# Power_Supply.net
KiCad netlist of a schematic drawn in Altium Designer
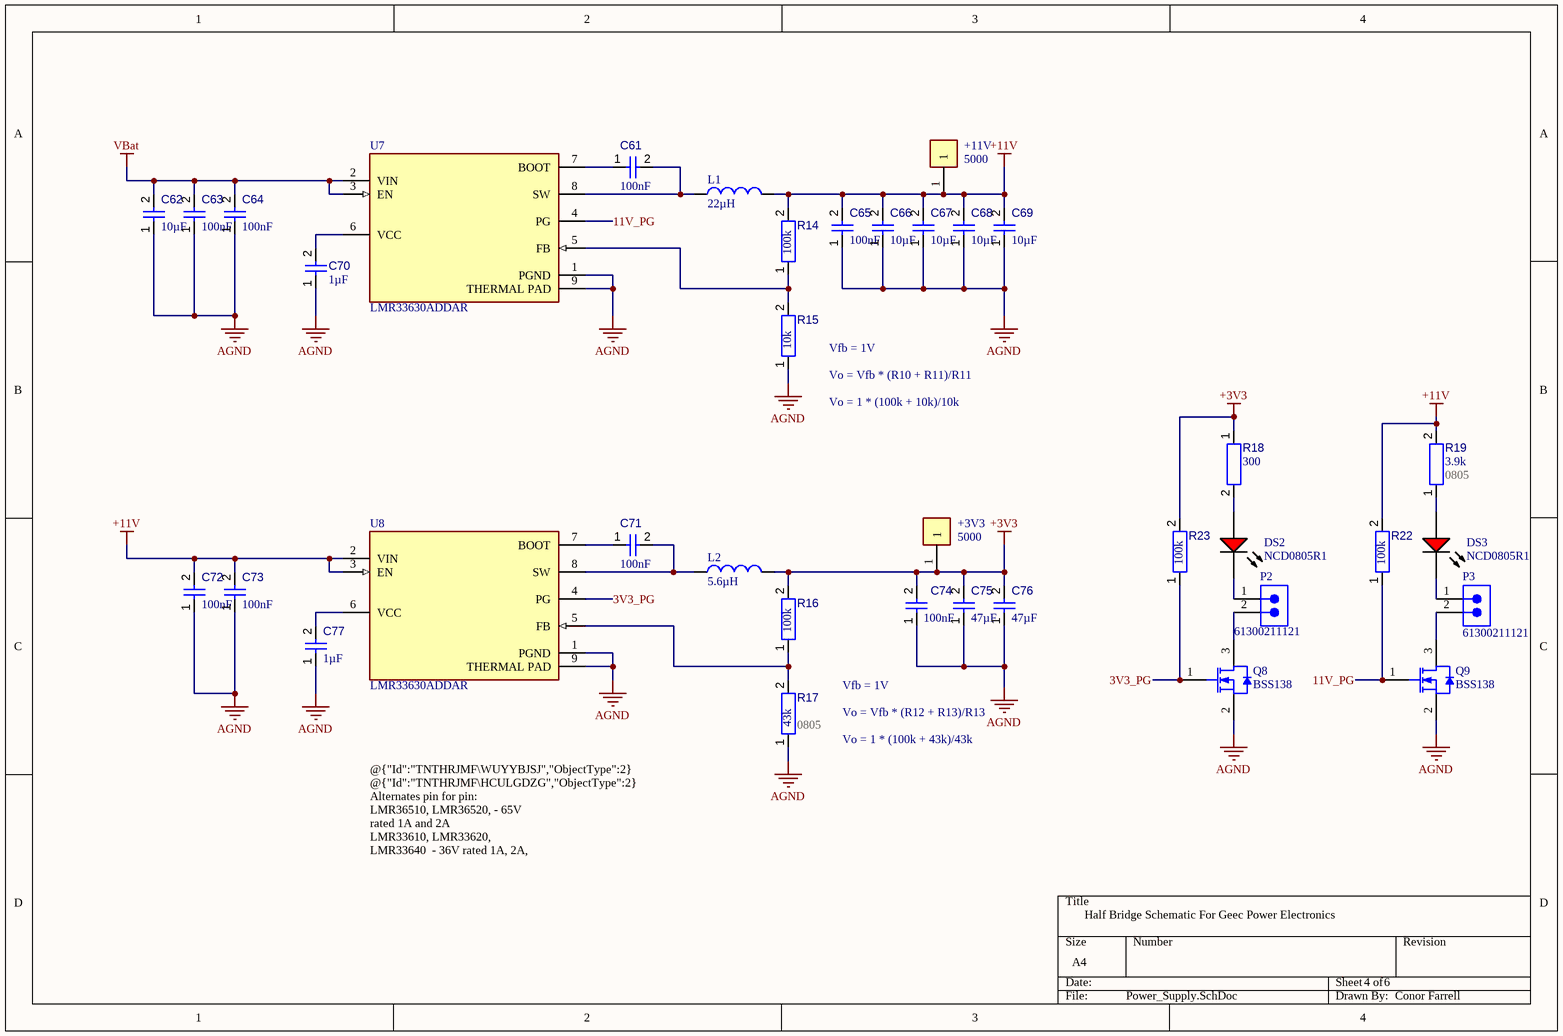
[diagram p0: Power_Supply.SchDoc]

(export (version "E")
  (design (tool "Eeschema 10.0.6"))
  (components
    (comp (ref "+3V3")
      (value "5000")
      (footprint "FP-5000-MFG")
      (description "Cable Wrap, 1/2 Inch, Polyethylene, Natural, 50 Ft, Spirap Series")
      (libsource (lib "University of Galway") (part "1e4615820a309e3ce90f9e6d957b7fa"))
    )
    (comp (ref "+11V")
      (value "5000")
      (footprint "FP-5000-MFG")
      (description "Cable Wrap, 1/2 Inch, Polyethylene, Natural, 50 Ft, Spirap Series")
      (libsource (lib "University of Galway") (part "1e4615820a309e3ce90f9e6d957b7fa"))
    )
    (comp (ref "C61")
      (value "100nF")
      (footprint "CAPC3216X190X55ML30T25")
      (description "50V 100nF X7R ±10% 1206 Multilayer Ceramic Capacitors MLCC - SMD/SMT ROHS")
      (fields (field (name "TOLERANCE") "10%") (field (name "Comment") "CL31B104KBCNNNC"))
      (libsource (lib "University of Galway") (part "CAP-NP-2"))
    )
    (comp (ref "C62")
      (value "10µF")
      (footprint "FP-GCM32E-0_3-IPC_C")
      (description "50V 10uF X7S ±10% 1210 Multilayer Ceramic Capacitors MLCC - SMD/SMT ROHS")
      (fields (field (name "TOLERANCE") "10%") (field (name "Comment") "GCM32EC71H106KA03L"))
      (libsource (lib "University of Galway") (part "CAP-NP-2"))
    )
    (comp (ref "C63")
      (value "100nF")
      (footprint "CAPC3216X190X55ML30T25")
      (description "50V 100nF X7R ±10% 1206 Multilayer Ceramic Capacitors MLCC - SMD/SMT ROHS")
      (fields (field (name "TOLERANCE") "10%") (field (name "Comment") "CL31B104KBCNNNC"))
      (libsource (lib "University of Galway") (part "CAP-NP-2"))
    )
    (comp (ref "C64")
      (value "100nF")
      (footprint "CAPC3216X190X55ML30T25")
      (description "50V 100nF X7R ±10% 1206 Multilayer Ceramic Capacitors MLCC - SMD/SMT ROHS")
      (fields (field (name "TOLERANCE") "10%") (field (name "Comment") "CL31B104KBCNNNC"))
      (libsource (lib "University of Galway") (part "CAP-NP-2"))
    )
    (comp (ref "C65")
      (value "100nF")
      (footprint "CAPC3216X190X55ML30T25")
      (description "50V 100nF X7R ±10% 1206 Multilayer Ceramic Capacitors MLCC - SMD/SMT ROHS")
      (fields (field (name "TOLERANCE") "10%") (field (name "Comment") "CL31B104KBCNNNC"))
      (libsource (lib "University of Galway") (part "CAP-NP-2"))
    )
    (comp (ref "C66")
      (value "10µF")
      (footprint "FP-GCM32E-0_3-IPC_C")
      (description "50V 10uF X7S ±10% 1210 Multilayer Ceramic Capacitors MLCC - SMD/SMT ROHS")
      (fields (field (name "TOLERANCE") "10%") (field (name "Comment") "GCM32EC71H106KA03L"))
      (libsource (lib "University of Galway") (part "CAP-NP-2"))
    )
    (comp (ref "C67")
      (value "10µF")
      (footprint "FP-GCM32E-0_3-IPC_C")
      (description "50V 10uF X7S ±10% 1210 Multilayer Ceramic Capacitors MLCC - SMD/SMT ROHS")
      (fields (field (name "TOLERANCE") "10%") (field (name "Comment") "GCM32EC71H106KA03L"))
      (libsource (lib "University of Galway") (part "CAP-NP-2"))
    )
    (comp (ref "C68")
      (value "10µF")
      (footprint "FP-GCM32E-0_3-IPC_C")
      (description "50V 10uF X7S ±10% 1210 Multilayer Ceramic Capacitors MLCC - SMD/SMT ROHS")
      (fields (field (name "TOLERANCE") "10%") (field (name "Comment") "GCM32EC71H106KA03L"))
      (libsource (lib "University of Galway") (part "CAP-NP-2"))
    )
    (comp (ref "C69")
      (value "10µF")
      (footprint "FP-GCM32E-0_3-IPC_C")
      (description "50V 10uF X7S ±10% 1210 Multilayer Ceramic Capacitors MLCC - SMD/SMT ROHS")
      (fields (field (name "TOLERANCE") "10%") (field (name "Comment") "GCM32EC71H106KA03L"))
      (libsource (lib "University of Galway") (part "CAP-NP-2"))
    )
    (comp (ref "C70")
      (value "1µF")
      (footprint "CAPC3216X180X20ML20")
      (fields (field (name "TOLERANCE") "10%") (field (name "Comment") "CL31B105KBHNNNE"))
      (libsource (lib "University of Galway") (part "CAP-NP-2"))
    )
    (comp (ref "C71")
      (value "100nF")
      (footprint "CAPC3216X190X55ML30T25")
      (description "50V 100nF X7R ±10% 1206 Multilayer Ceramic Capacitors MLCC - SMD/SMT ROHS")
      (fields (field (name "TOLERANCE") "10%") (field (name "Comment") "CL31B104KBCNNNC"))
      (libsource (lib "University of Galway") (part "CAP-NP-2"))
    )
    (comp (ref "C72")
      (value "100nF")
      (footprint "CAPC3216X190X55ML30T25")
      (description "50V 100nF X7R ±10% 1206 Multilayer Ceramic Capacitors MLCC - SMD/SMT ROHS")
      (fields (field (name "TOLERANCE") "10%") (field (name "Comment") "CL31B104KBCNNNC"))
      (libsource (lib "University of Galway") (part "CAP-NP-2"))
    )
    (comp (ref "C73")
      (value "100nF")
      (footprint "CAPC3216X190X55ML30T25")
      (description "50V 100nF X7R ±10% 1206 Multilayer Ceramic Capacitors MLCC - SMD/SMT ROHS")
      (fields (field (name "TOLERANCE") "10%") (field (name "Comment") "CL31B104KBCNNNC"))
      (libsource (lib "University of Galway") (part "CAP-NP-2"))
    )
    (comp (ref "C74")
      (value "100nF")
      (footprint "CAPC3216X190X55ML30T25")
      (description "50V 100nF X7R ±10% 1206 Multilayer Ceramic Capacitors MLCC - SMD/SMT ROHS")
      (fields (field (name "TOLERANCE") "10%") (field (name "Comment") "CL31B104KBCNNNC"))
      (libsource (lib "University of Galway") (part "CAP-NP-2"))
    )
    (comp (ref "C75")
      (value "47µF")
      (footprint "CAPC3216X190X55LL30T25")
      (fields (field (name "TOLERANCE") "20%") (field (name "Comment") "CL31A476MPHNNNE"))
      (libsource (lib "University of Galway") (part "CAP-NP-2"))
    )
    (comp (ref "C76")
      (value "47µF")
      (footprint "CAPC3216X190X55LL30T25")
      (fields (field (name "TOLERANCE") "20%") (field (name "Comment") "CL31A476MPHNNNE"))
      (libsource (lib "University of Galway") (part "CAP-NP-2"))
    )
    (comp (ref "C77")
      (value "1µF")
      (footprint "CAPC3216X180X20ML20")
      (fields (field (name "TOLERANCE") "10%") (field (name "Comment") "CL31B105KBHNNNE"))
      (libsource (lib "University of Galway") (part "CAP-NP-2"))
    )
    (comp (ref "DS2")
      (value "NCD0805R1")
      (footprint "Copy of WL-SMCW_0805_150080xx75000")
      (libsource (lib "University of Galway") (part "LED-RED-AK-2"))
    )
    (comp (ref "DS3")
      (value "NCD0805R1")
      (footprint "Copy of WL-SMCW_0805_150080xx75000")
      (libsource (lib "University of Galway") (part "LED-RED-AK-2"))
    )
    (comp (ref "L1")
      (value "22µH")
      (footprint "INDP127127X85N")
      (description "Inductor Power Shielded Wirewound 22uH 20% 1KHz 23Q-Factor Ferrite 3.5A 0.043Ohm DCR T/R")
      (fields (field (name "TOLERANCE") "20%") (field (name "Comment") "SRR1208-220ML"))
      (libsource (lib "University of Galway") (part "IND-2"))
    )
    (comp (ref "L2")
      (value "5.6µH")
      (footprint "INDP125125X60N")
      (description "Ind Power Shielded Wirewound 5.6uH 30% 100KHz 19Q-Factor Ferrite 6.7A T/R")
      (fields (field (name "TOLERANCE") "30%") (field (name "Comment") "SRR1260A-5R6Y"))
      (libsource (lib "University of Galway") (part "IND-2"))
    )
    (comp (ref "P2")
      (value "61300211121")
      (footprint "61300211121")
      (description "WR-PHD Pin Header, THT, Vertical, pitch 2.54mm, 1 Row, 2P")
      (fields (field (name "MANUFACTURER") "Wurth Elektronik"))
      (libsource (lib "University of Galway") (part "62000211121"))
    )
    (comp (ref "P3")
      (value "61300211121")
      (footprint "61300211121")
      (description "WR-PHD Pin Header, THT, Vertical, pitch 2.54mm, 1 Row, 2P")
      (fields (field (name "MANUFACTURER") "Wurth Elektronik"))
      (libsource (lib "University of Galway") (part "62000211121"))
    )
    (comp (ref "Q8")
      (value "BSS138")
      (footprint "FAIR-SOT23-3_V")
      (fields (field (name "MANUFACTURER") "Fairchild") (field (name "POWER") "360mW"))
      (libsource (lib "University of Galway") (part "NEMOS-GSD-3"))
    )
    (comp (ref "Q9")
      (value "BSS138")
      (footprint "FAIR-SOT23-3_V")
      (fields (field (name "MANUFACTURER") "Fairchild") (field (name "POWER") "360mW"))
      (libsource (lib "University of Galway") (part "NEMOS-GSD-3"))
    )
    (comp (ref "R14")
      (value "100k")
      (footprint "RESC3216X60X45NL15T20")
      (fields (field (name "TOLERANCE") "1%") (field (name "Comment") "1206W4F1003T5E"))
      (libsource (lib "University of Galway") (part "RES-2"))
    )
    (comp (ref "R15")
      (value "10k")
      (footprint "RESC3216X60X45ML15T20")
      (description "Res Thick Film 1206 10K Ohm 1% 0.25W(1/4W) ±100ppm/C Pad SMD T/R")
      (fields (field (name "Comment") "1206W4F1002T5E"))
      (libsource (lib "University of Galway") (part "RES-2"))
    )
    (comp (ref "R16")
      (value "100k")
      (footprint "RESC3216X60X45NL15T20")
      (fields (field (name "TOLERANCE") "1%") (field (name "Comment") "1206W4F1003T5E"))
      (libsource (lib "University of Galway") (part "RES-2"))
    )
    (comp (ref "R17")
      (value "43k")
      (footprint "RESC0805(2012)_L")
      (description "125mW Thick Film Resistors 150V ±100ppm/℃ ±1% 43kΩ 0805 Chip Resistor - Surface Mount ROHS")
      (fields
        (field (name "TOLERANCE") "1%")
        (field (name "POWER") "125mW")
        (field (name "CASE/PACKAGE") "0805")
      )
      (libsource (lib "University of Galway") (part "RES-2"))
    )
    (comp (ref "R18")
      (value "300")
      (footprint "RESC3216X89X51NL25T25")
      (description "250mW Thick Film Resistors 200V ±100ppm/℃ ±1% 300Ω 1206 Chip Resistor - Surface Mount ROHS")
      (fields (field (name "Comment") "1206W4F3000T5E"))
      (libsource (lib "University of Galway") (part "RES-2"))
    )
    (comp (ref "R19")
      (value "3.9k")
      (footprint "RESC2013X60X35ML10T20")
      (description "Res Thick Film 0805 3.9K Ohm 1% 0.125W(1/8W) ±100ppm/C Pad SMD T/R")
      (fields
        (field (name "CASE/PACKAGE") "0805")
        (field (name "POWER") "125mW")
        (field (name "Comment") "0805W8F3901T5E")
      )
      (libsource (lib "University of Galway") (part "RES-2"))
    )
    (comp (ref "R22")
      (value "100k")
      (footprint "RESC3216X60X45NL15T20")
      (fields (field (name "TOLERANCE") "1%") (field (name "Comment") "1206W4F1003T5E"))
      (libsource (lib "University of Galway") (part "RES-2"))
    )
    (comp (ref "R23")
      (value "100k")
      (footprint "RESC3216X60X45NL15T20")
      (fields (field (name "TOLERANCE") "1%") (field (name "Comment") "1206W4F1003T5E"))
      (libsource (lib "University of Galway") (part "RES-2"))
    )
    (comp (ref "U7")
      (value "LMR33630ADDAR")
      (footprint "SOIC127P600X170_HS-9N")
      (libsource (lib "University of Galway") (part "6a354f5098e7f60ae670b755afcc2ec"))
    )
    (comp (ref "U8")
      (value "LMR33630ADDAR")
      (footprint "SOIC127P600X170_HS-9N")
      (libsource (lib "University of Galway") (part "6a354f5098e7f60ae670b755afcc2ec"))
    )
  )
  (nets
    (net (code "1") (name "+3V3") (class "Default")
      (node (ref "+3V3") (pin "1") (pinfunction "1_1") (pintype "passive"))
      (node (ref "C74") (pin "2") (pinfunction "2_2") (pintype "passive"))
      (node (ref "C75") (pin "2") (pinfunction "2_2") (pintype "passive"))
      (node (ref "C76") (pin "2") (pinfunction "2_2") (pintype "passive"))
      (node (ref "L2") (pin "2") (pinfunction "2_2") (pintype "passive"))
      (node (ref "R16") (pin "2") (pinfunction "2_2") (pintype "passive"))
      (node (ref "R18") (pin "1") (pinfunction "1_1") (pintype "passive"))
      (node (ref "R23") (pin "2") (pinfunction "2_2") (pintype "passive"))
    )
    (net (code "2") (name "+11V") (class "Default")
      (node (ref "+11V") (pin "1") (pinfunction "1_1") (pintype "passive"))
      (node (ref "C65") (pin "2") (pinfunction "2_2") (pintype "passive"))
      (node (ref "C66") (pin "2") (pinfunction "2_2") (pintype "passive"))
      (node (ref "C67") (pin "2") (pinfunction "2_2") (pintype "passive"))
      (node (ref "C68") (pin "2") (pinfunction "2_2") (pintype "passive"))
      (node (ref "C69") (pin "2") (pinfunction "2_2") (pintype "passive"))
      (node (ref "C72") (pin "2") (pinfunction "2_2") (pintype "passive"))
      (node (ref "C73") (pin "2") (pinfunction "2_2") (pintype "passive"))
      (node (ref "L1") (pin "2") (pinfunction "2_2") (pintype "passive"))
      (node (ref "R14") (pin "2") (pinfunction "2_2") (pintype "passive"))
      (node (ref "R19") (pin "2") (pinfunction "2_2") (pintype "passive"))
      (node (ref "R22") (pin "2") (pinfunction "2_2") (pintype "passive"))
      (node (ref "U8") (pin "2") (pinfunction "VIN_2") (pintype "power_in"))
      (node (ref "U8") (pin "3") (pinfunction "EN_3") (pintype "input"))
    )
    (net (code "3") (name "/3V3_PG") (class "Default")
      (node (ref "Q8") (pin "1") (pinfunction "G_1") (pintype "passive"))
      (node (ref "R23") (pin "1") (pinfunction "1_1") (pintype "passive"))
      (node (ref "U8") (pin "4") (pinfunction "PG_4") (pintype "open_collector"))
    )
    (net (code "4") (name "/11V_PG") (class "Default")
      (node (ref "Q9") (pin "1") (pinfunction "G_1") (pintype "passive"))
      (node (ref "R22") (pin "1") (pinfunction "1_1") (pintype "passive"))
      (node (ref "U7") (pin "4") (pinfunction "PG_4") (pintype "open_collector"))
    )
    (net (code "5") (name "AGND") (class "Default")
      (node (ref "C62") (pin "1") (pinfunction "1_1") (pintype "passive"))
      (node (ref "C63") (pin "1") (pinfunction "1_1") (pintype "passive"))
      (node (ref "C64") (pin "1") (pinfunction "1_1") (pintype "passive"))
      (node (ref "C65") (pin "1") (pinfunction "1_1") (pintype "passive"))
      (node (ref "C66") (pin "1") (pinfunction "1_1") (pintype "passive"))
      (node (ref "C67") (pin "1") (pinfunction "1_1") (pintype "passive"))
      (node (ref "C68") (pin "1") (pinfunction "1_1") (pintype "passive"))
      (node (ref "C69") (pin "1") (pinfunction "1_1") (pintype "passive"))
      (node (ref "C70") (pin "1") (pinfunction "1_1") (pintype "passive"))
      (node (ref "C72") (pin "1") (pinfunction "1_1") (pintype "passive"))
      (node (ref "C73") (pin "1") (pinfunction "1_1") (pintype "passive"))
      (node (ref "C74") (pin "1") (pinfunction "1_1") (pintype "passive"))
      (node (ref "C75") (pin "1") (pinfunction "1_1") (pintype "passive"))
      (node (ref "C76") (pin "1") (pinfunction "1_1") (pintype "passive"))
      (node (ref "C77") (pin "1") (pinfunction "1_1") (pintype "passive"))
      (node (ref "Q8") (pin "2") (pinfunction "S_2") (pintype "passive"))
      (node (ref "Q9") (pin "2") (pinfunction "S_2") (pintype "passive"))
      (node (ref "R15") (pin "1") (pinfunction "1_1") (pintype "passive"))
      (node (ref "R17") (pin "1") (pinfunction "1_1") (pintype "passive"))
      (node (ref "U7") (pin "1") (pinfunction "PGND_1") (pintype "power_in"))
      (node (ref "U7") (pin "9") (pinfunction "THERMAL_PAD_9") (pintype "passive"))
      (node (ref "U8") (pin "1") (pinfunction "PGND_1") (pintype "power_in"))
      (node (ref "U8") (pin "9") (pinfunction "THERMAL_PAD_9") (pintype "passive"))
    )
    (net (code "6") (name "Net-(DS2-A)") (class "Default")
      (node (ref "DS2") (pin "1") (pinfunction "A_1") (pintype "passive"))
      (node (ref "R18") (pin "2") (pinfunction "2_2") (pintype "passive"))
    )
    (net (code "7") (name "Net-(DS2-K)") (class "Default")
      (node (ref "DS2") (pin "2") (pinfunction "K_2") (pintype "passive"))
      (node (ref "P2") (pin "1") (pinfunction "1_1") (pintype "passive"))
    )
    (net (code "8") (name "Net-(DS3-A)") (class "Default")
      (node (ref "DS3") (pin "1") (pinfunction "A_1") (pintype "passive"))
      (node (ref "R19") (pin "1") (pinfunction "1_1") (pintype "passive"))
    )
    (net (code "9") (name "Net-(DS3-K)") (class "Default")
      (node (ref "DS3") (pin "2") (pinfunction "K_2") (pintype "passive"))
      (node (ref "P3") (pin "1") (pinfunction "1_1") (pintype "passive"))
    )
    (net (code "10") (name "Net-(Q8-D)") (class "Default")
      (node (ref "P2") (pin "2") (pinfunction "2_2") (pintype "passive"))
      (node (ref "Q8") (pin "3") (pinfunction "D_3") (pintype "passive"))
    )
    (net (code "11") (name "Net-(Q9-D)") (class "Default")
      (node (ref "P3") (pin "2") (pinfunction "2_2") (pintype "passive"))
      (node (ref "Q9") (pin "3") (pinfunction "D_3") (pintype "passive"))
    )
    (net (code "12") (name "Net-(U7-BOOT)") (class "Default")
      (node (ref "C61") (pin "1") (pinfunction "1_1") (pintype "passive"))
      (node (ref "U7") (pin "7") (pinfunction "BOOT_7") (pintype "passive"))
    )
    (net (code "13") (name "Net-(U7-FB)") (class "Default")
      (node (ref "R14") (pin "1") (pinfunction "1_1") (pintype "passive"))
      (node (ref "R15") (pin "2") (pinfunction "2_2") (pintype "passive"))
      (node (ref "U7") (pin "5") (pinfunction "FB_5") (pintype "input"))
    )
    (net (code "14") (name "Net-(U7-SW)") (class "Default")
      (node (ref "C61") (pin "2") (pinfunction "2_2") (pintype "passive"))
      (node (ref "L1") (pin "1") (pinfunction "1_1") (pintype "passive"))
      (node (ref "U7") (pin "8") (pinfunction "SW_8") (pintype "passive"))
    )
    (net (code "15") (name "Net-(U7-VCC)") (class "Default")
      (node (ref "C70") (pin "2") (pinfunction "2_2") (pintype "passive"))
      (node (ref "U7") (pin "6") (pinfunction "VCC_6") (pintype "power_in"))
    )
    (net (code "16") (name "Net-(U8-BOOT)") (class "Default")
      (node (ref "C71") (pin "1") (pinfunction "1_1") (pintype "passive"))
      (node (ref "U8") (pin "7") (pinfunction "BOOT_7") (pintype "passive"))
    )
    (net (code "17") (name "Net-(U8-FB)") (class "Default")
      (node (ref "R16") (pin "1") (pinfunction "1_1") (pintype "passive"))
      (node (ref "R17") (pin "2") (pinfunction "2_2") (pintype "passive"))
      (node (ref "U8") (pin "5") (pinfunction "FB_5") (pintype "input"))
    )
    (net (code "18") (name "Net-(U8-SW)") (class "Default")
      (node (ref "C71") (pin "2") (pinfunction "2_2") (pintype "passive"))
      (node (ref "L2") (pin "1") (pinfunction "1_1") (pintype "passive"))
      (node (ref "U8") (pin "8") (pinfunction "SW_8") (pintype "passive"))
    )
    (net (code "19") (name "Net-(U8-VCC)") (class "Default")
      (node (ref "C77") (pin "2") (pinfunction "2_2") (pintype "passive"))
      (node (ref "U8") (pin "6") (pinfunction "VCC_6") (pintype "power_in"))
    )
    (net (code "20") (name "VBat") (class "Default")
      (node (ref "C62") (pin "2") (pinfunction "2_2") (pintype "passive"))
      (node (ref "C63") (pin "2") (pinfunction "2_2") (pintype "passive"))
      (node (ref "C64") (pin "2") (pinfunction "2_2") (pintype "passive"))
      (node (ref "U7") (pin "2") (pinfunction "VIN_2") (pintype "power_in"))
      (node (ref "U7") (pin "3") (pinfunction "EN_3") (pintype "input"))
    )
  )
)
